# ssr.net
KiCad netlist of a schematic drawn in EAGLE
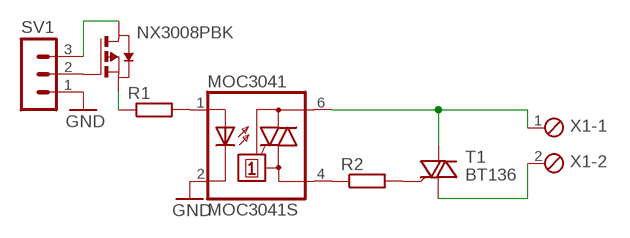
[diagram p0: schematic, sheet 1]

(export (version "E")
  (design (tool "Eeschema 10.0.6"))
  (components
    (comp (ref "MOC3041")
      (value "MOC3041S")
      (footprint "eagle-import:DIL6-SMD")
      (fields
        (field (name "MF") "FAIRCHILD SEMICONDUCTOR")
        (field (name "MPN") "MOC3041S-M")
        (field (name "MPN_1") "MOC3041S-M")
        (field (name "OC_FARNELL") "unknown")
        (field (name "OC_NEWARK") "05C2885")
      )
      (libsource (lib "eagle-import") (part "MOC30S41"))
    )
    (comp (ref "NX3008PBK")
      (value "PMOSSOT23")
      (footprint "eagle-import:SOT-23")
      (libsource (lib "eagle-import") (part "PMOSSOT23"))
    )
    (comp (ref "R1")
      (value "R-EU_R1206")
      (footprint "eagle-import:R1206")
      (libsource (lib "eagle-import") (part "R-EU_R1206"))
    )
    (comp (ref "R2")
      (value "R-EU_R1206")
      (footprint "eagle-import:R1206")
      (libsource (lib "eagle-import") (part "R-EU_R1206"))
    )
    (comp (ref "SV1")
      (value "MA03-1")
      (footprint "eagle-import:MA03-1")
      (libsource (lib "eagle-import") (part "MA03-1"))
    )
    (comp (ref "T1")
      (value "BT136")
      (footprint "eagle-import:TO220AB")
      (libsource (lib "eagle-import") (part "BT136"))
    )
    (comp (ref "X1")
      (value "MPT2")
      (footprint "eagle-import:2POL254")
      (libsource (lib "eagle-import") (part "MPT2"))
    )
  )
  (nets
    (net (code "1") (name "GND") (class "Default")
      (node (ref "MOC3041") (pin "2") (pinfunction "C_2") (pintype "passive"))
      (node (ref "SV1") (pin "1") (pinfunction "1_1") (pintype "passive"))
    )
    (net (code "2") (name "Net-(MOC3041-A)") (class "Default")
      (node (ref "MOC3041") (pin "1") (pinfunction "A_1") (pintype "passive"))
      (node (ref "R1") (pin "2") (pinfunction "2_2") (pintype "passive"))
    )
    (net (code "3") (name "Net-(MOC3041-A1)") (class "Default")
      (node (ref "MOC3041") (pin "4") (pinfunction "A1_4") (pintype "passive"))
      (node (ref "R2") (pin "1") (pinfunction "1_1") (pintype "passive"))
    )
    (net (code "4") (name "Net-(MOC3041-A2)") (class "Default")
      (node (ref "MOC3041") (pin "6") (pinfunction "A2_6") (pintype "passive"))
      (node (ref "T1") (pin "2") (pinfunction "A2_2") (pintype "passive"))
      (node (ref "X1") (pin "1") (pinfunction "1_1") (pintype "passive"))
    )
    (net (code "5") (name "Net-(NX3008PBK-D)") (class "Default")
      (node (ref "NX3008PBK") (pin "1") (pinfunction "D_1") (pintype "passive"))
      (node (ref "SV1") (pin "3") (pinfunction "3_3") (pintype "passive"))
    )
    (net (code "6") (name "Net-(NX3008PBK-G)") (class "Default")
      (node (ref "NX3008PBK") (pin "3") (pinfunction "G_3") (pintype "passive"))
      (node (ref "SV1") (pin "2") (pinfunction "2_2") (pintype "passive"))
    )
    (net (code "7") (name "Net-(NX3008PBK-S)") (class "Default")
      (node (ref "NX3008PBK") (pin "2") (pinfunction "S_2") (pintype "passive"))
      (node (ref "R1") (pin "1") (pinfunction "1_1") (pintype "passive"))
    )
    (net (code "8") (name "Net-(T1-A1)") (class "Default")
      (node (ref "T1") (pin "1") (pinfunction "A1_1") (pintype "passive"))
      (node (ref "X1") (pin "2") (pinfunction "1_2") (pintype "passive"))
    )
    (net (code "9") (name "Net-(T1-G)") (class "Default")
      (node (ref "R2") (pin "2") (pinfunction "2_2") (pintype "passive"))
      (node (ref "T1") (pin "3") (pinfunction "G_3") (pintype "passive"))
    )
  )
)
